# DGCtrl.net
KiCad netlist of a schematic drawn in Altium Designer
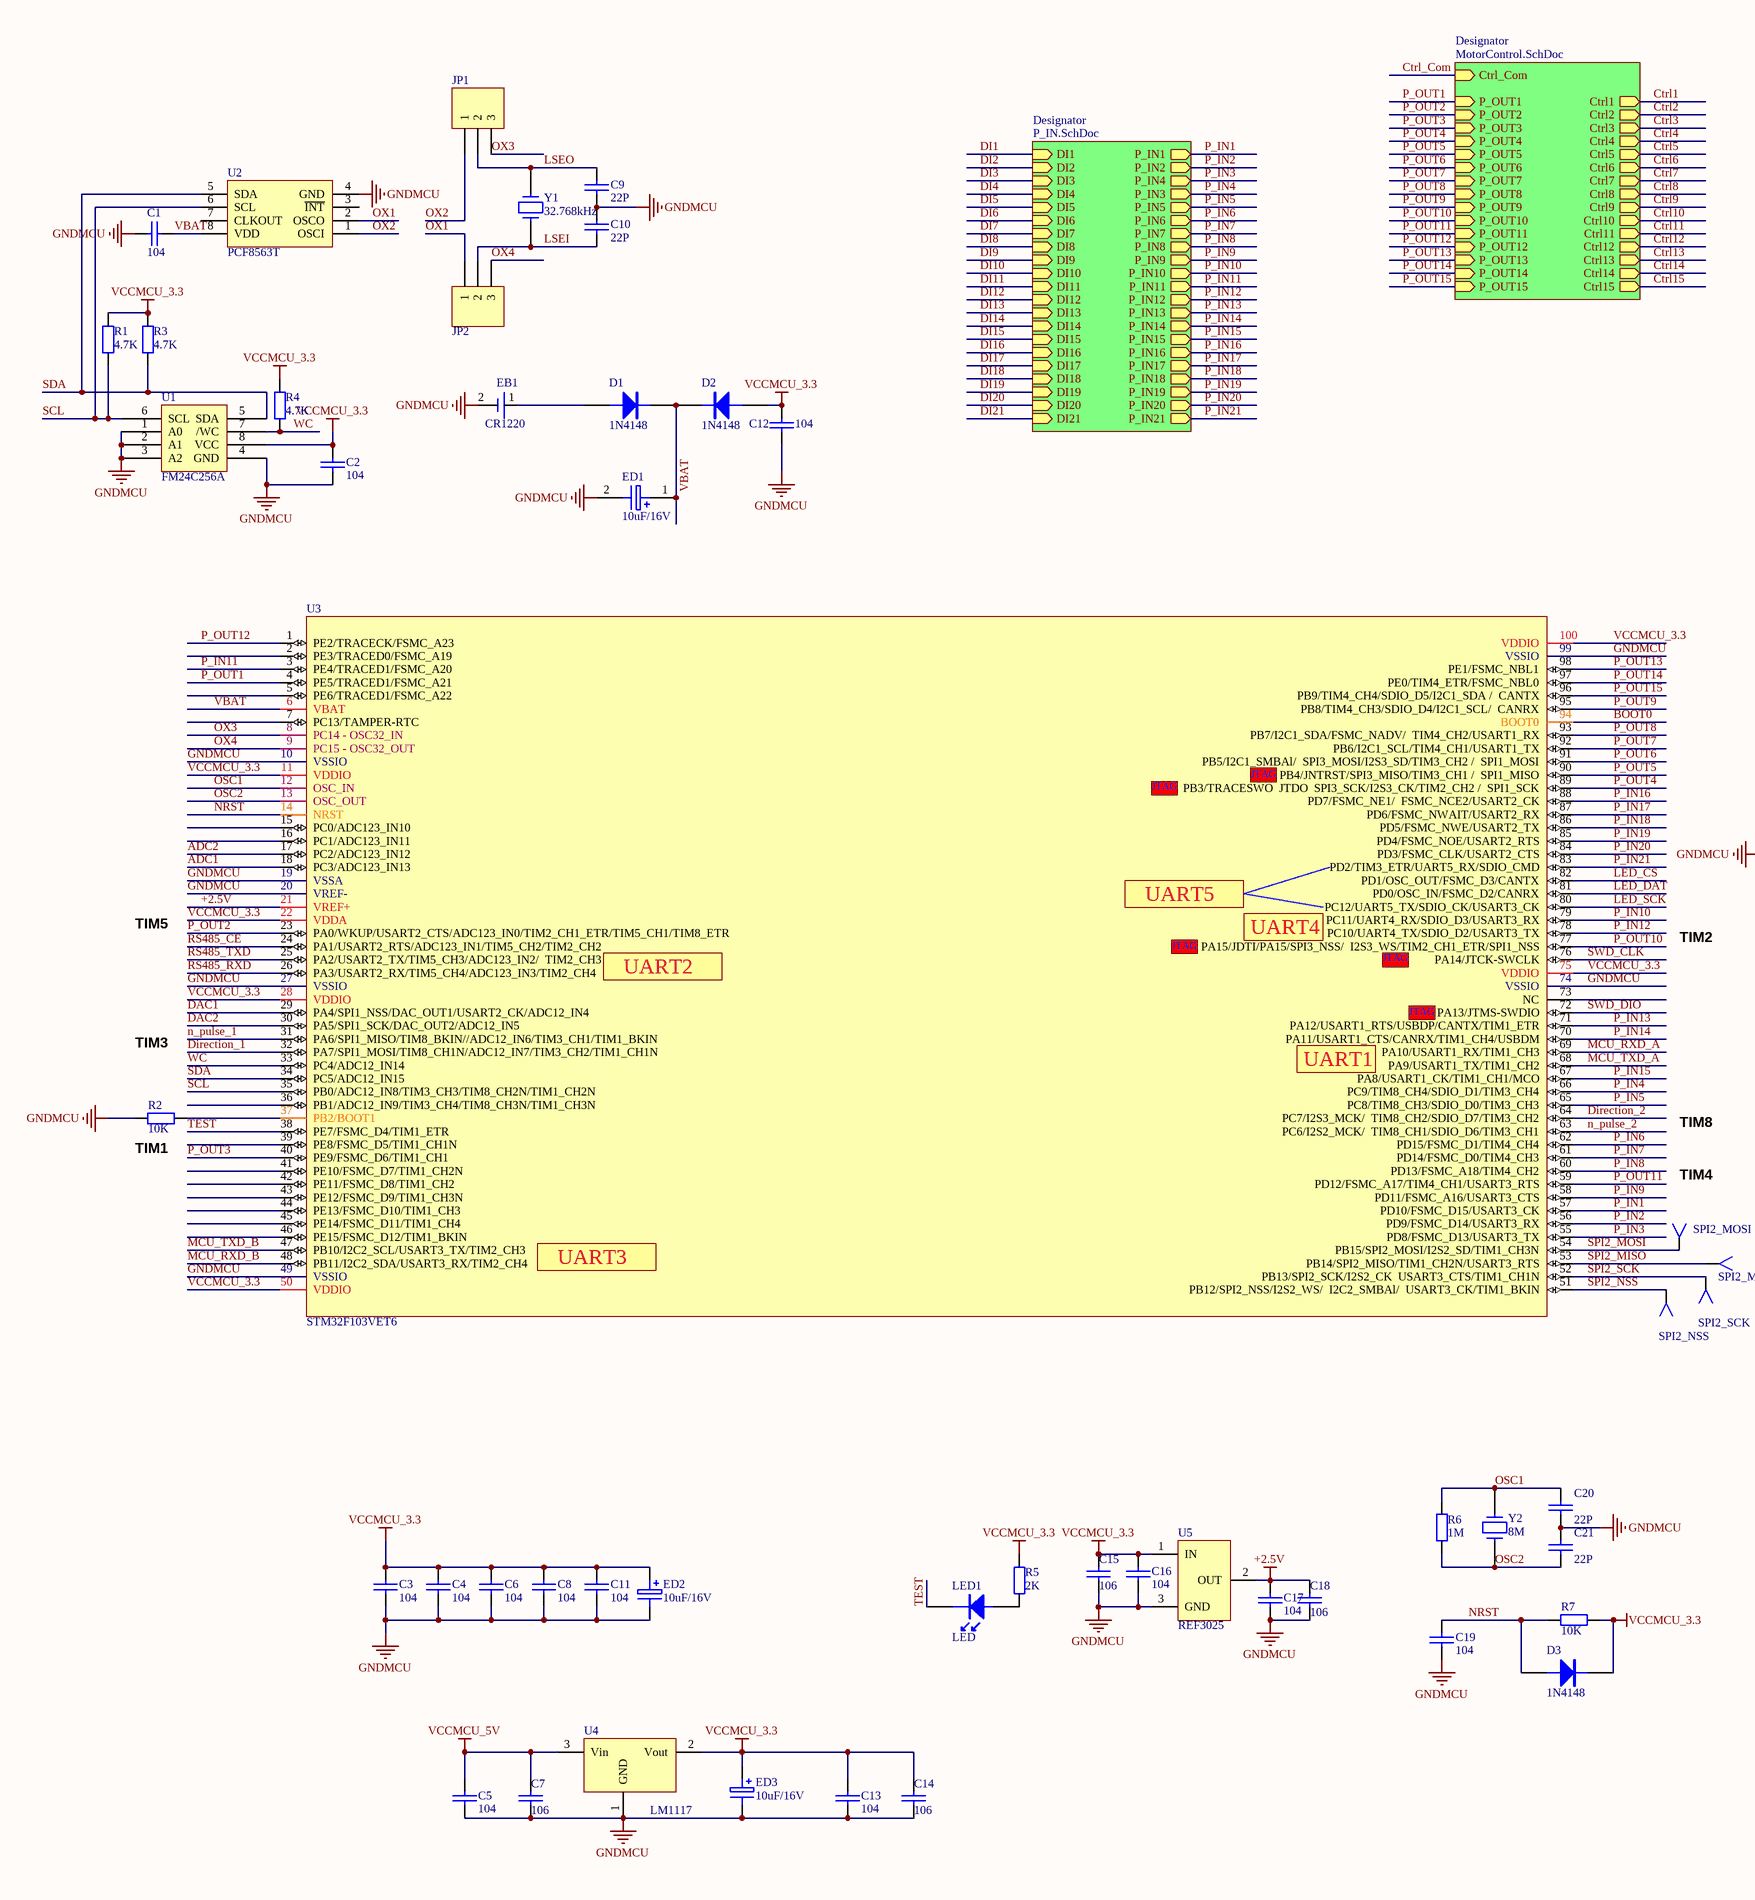
[diagram p0: DGCtrl.SchDoc, left]
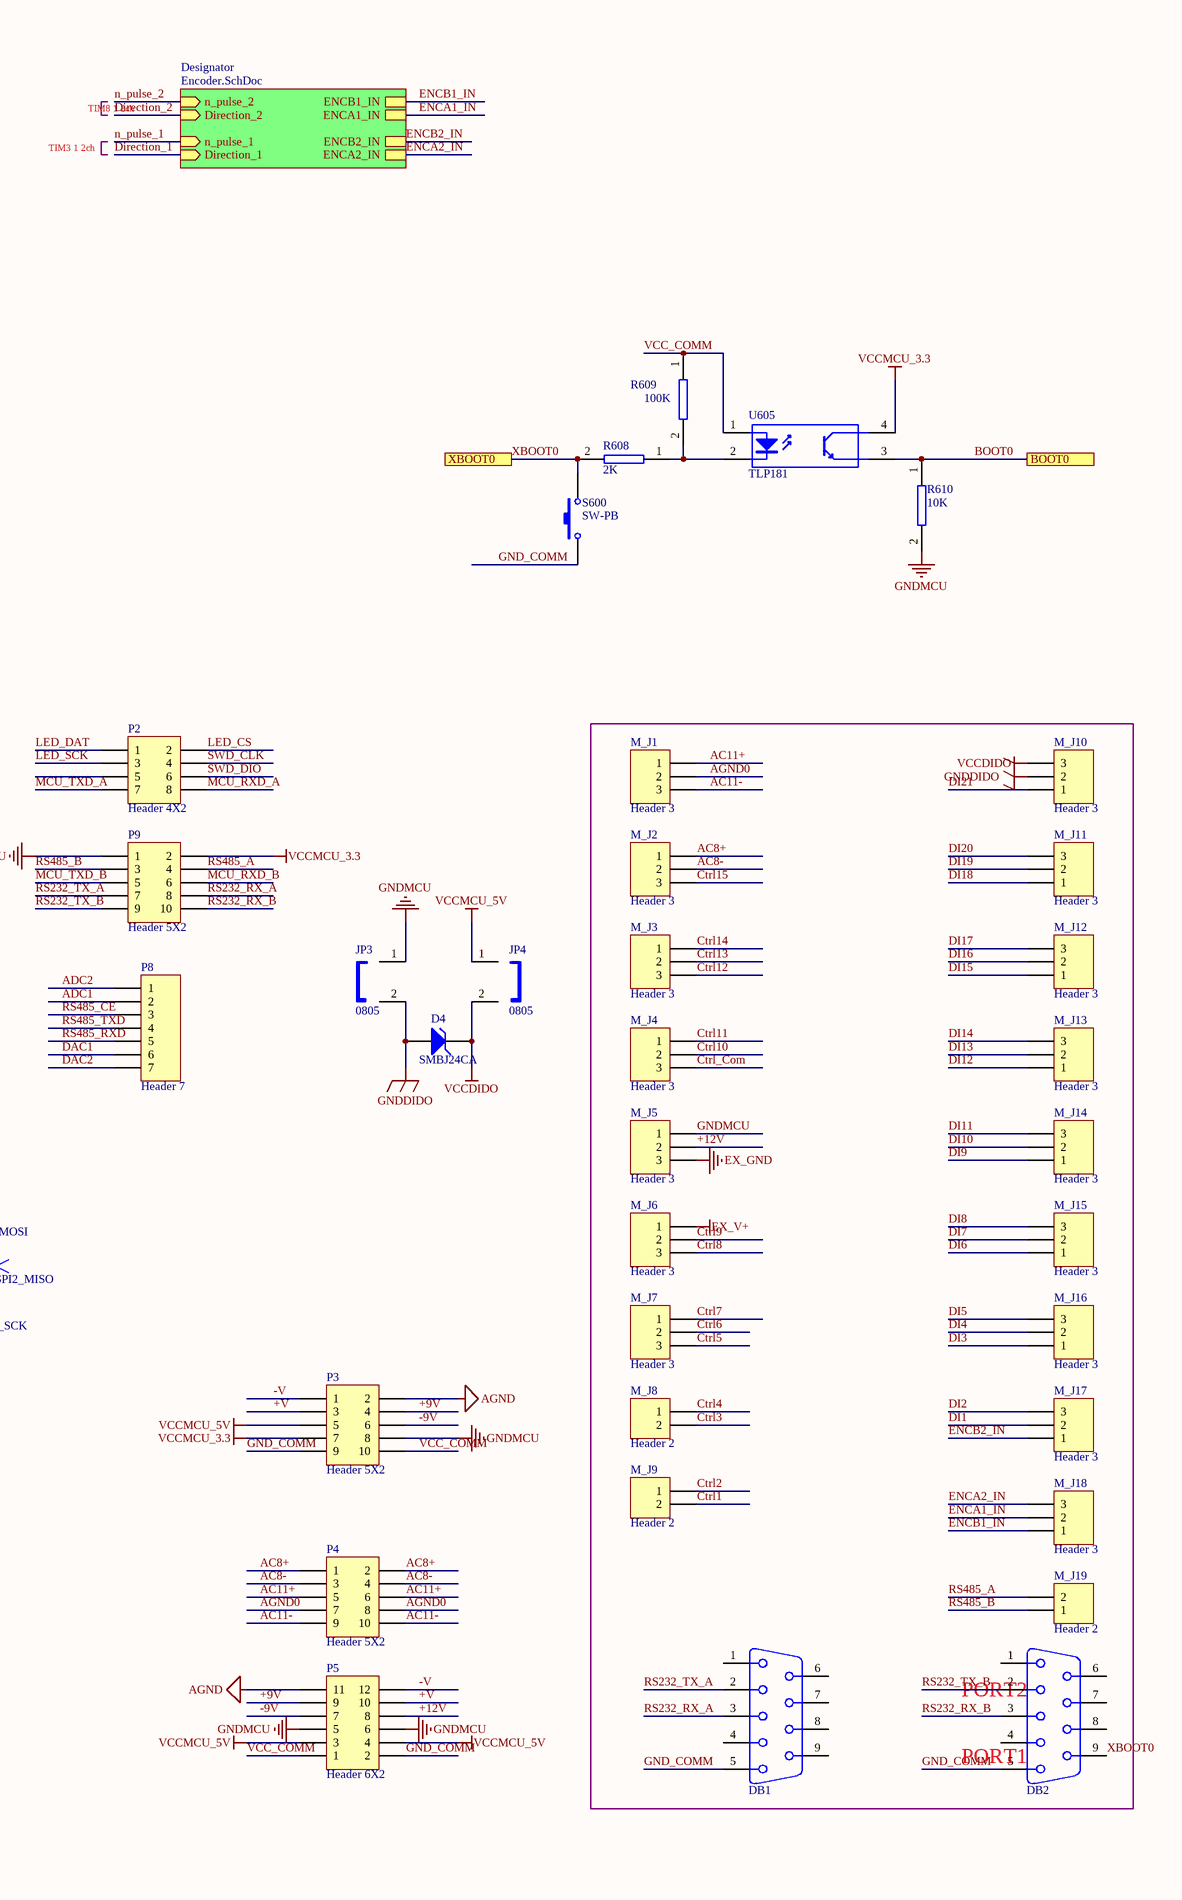
[diagram p1: DGCtrl.SchDoc, right]

(export (version "E")
  (design (tool "Eeschema 10.0.6"))
  (components
    (comp (ref "C1")
      (value "104")
      (footprint "CAPC_E0805_2012X70N")
      (description "Capacitor")
      (libsource (lib "YGInfoSCHLib") (part "CAP"))
    )
    (comp (ref "C2")
      (value "104")
      (footprint "CAPC_E0805_2012X70N")
      (description "Capacitor")
      (libsource (lib "YGInfoSCHLib") (part "CAP"))
    )
    (comp (ref "C3")
      (value "104")
      (footprint "CAPC_E0805_2012X70N")
      (description "Capacitor")
      (libsource (lib "YGInfoSCHLib") (part "CAP"))
    )
    (comp (ref "C4")
      (value "104")
      (footprint "CAPC_E0805_2012X70N")
      (description "Capacitor")
      (libsource (lib "YGInfoSCHLib") (part "CAP"))
    )
    (comp (ref "C5")
      (value "104")
      (footprint "CAPC_E0805_2012X70N")
      (description "Capacitor")
      (libsource (lib "YGInfoSCHLib") (part "CAP"))
    )
    (comp (ref "C6")
      (value "104")
      (footprint "CAPC_E0805_2012X70N")
      (description "Capacitor")
      (libsource (lib "YGInfoSCHLib") (part "CAP"))
    )
    (comp (ref "C7")
      (value "106")
      (footprint "CAPC_E0805_2012X70N")
      (description "Capacitor")
      (libsource (lib "YGInfoSCHLib") (part "CAP"))
    )
    (comp (ref "C8")
      (value "104")
      (footprint "CAPC_E0805_2012X70N")
      (description "Capacitor")
      (libsource (lib "YGInfoSCHLib") (part "CAP"))
    )
    (comp (ref "C9")
      (value "22P")
      (footprint "CAPC_E0805_2012X70N")
      (description "Capacitor")
      (libsource (lib "YGInfoSCHLib") (part "CAP"))
    )
    (comp (ref "C10")
      (value "22P")
      (footprint "CAPC_E0805_2012X70N")
      (description "Capacitor")
      (libsource (lib "YGInfoSCHLib") (part "CAP"))
    )
    (comp (ref "C11")
      (value "104")
      (footprint "CAPC_E0805_2012X70N")
      (description "Capacitor")
      (libsource (lib "YGInfoSCHLib") (part "CAP"))
    )
    (comp (ref "C12")
      (value "104")
      (footprint "CAPC_E0805_2012X70N")
      (description "Capacitor")
      (libsource (lib "YGInfoSCHLib") (part "CAP"))
    )
    (comp (ref "C13")
      (value "104")
      (footprint "CAPC_E0805_2012X70N")
      (description "Capacitor")
      (libsource (lib "YGInfoSCHLib") (part "CAP"))
    )
    (comp (ref "C14")
      (value "106")
      (footprint "CAPC_E0805_2012X70N")
      (description "Capacitor")
      (libsource (lib "YGInfoSCHLib") (part "CAP"))
    )
    (comp (ref "C15")
      (value "106")
      (footprint "CAPC_E0805_2012X70N")
      (description "Capacitor")
      (libsource (lib "YGInfoSCHLib") (part "CAP"))
    )
    (comp (ref "C16")
      (value "104")
      (footprint "CAPC_E0805_2012X70N")
      (description "Capacitor")
      (libsource (lib "YGInfoSCHLib") (part "CAP"))
    )
    (comp (ref "C17")
      (value "104")
      (footprint "CAPC_E0805_2012X70N")
      (description "Capacitor")
      (libsource (lib "YGInfoSCHLib") (part "CAP"))
    )
    (comp (ref "C18")
      (value "106")
      (footprint "CAPC_E0805_2012X70N")
      (description "Capacitor")
      (libsource (lib "YGInfoSCHLib") (part "CAP"))
    )
    (comp (ref "C19")
      (value "104")
      (footprint "CAPC_E0805_2012X70N")
      (description "Capacitor")
      (libsource (lib "YGInfoSCHLib") (part "CAP"))
    )
    (comp (ref "C20")
      (value "22P")
      (footprint "CAPC_E0805_2012X70N")
      (description "Capacitor")
      (libsource (lib "YGInfoSCHLib") (part "CAP"))
    )
    (comp (ref "C21")
      (value "22P")
      (footprint "CAPC_E0805_2012X70N")
      (description "Capacitor")
      (libsource (lib "YGInfoSCHLib") (part "CAP"))
    )
    (comp (ref "D1")
      (value "1N4148")
      (footprint "N4148")
      (description "Diode")
      (libsource (lib "YGInfoSCHLib") (part "DIODE"))
    )
    (comp (ref "D2")
      (value "1N4148")
      (footprint "N4148")
      (description "Diode")
      (libsource (lib "YGInfoSCHLib") (part "DIODE"))
    )
    (comp (ref "D3")
      (value "1N4148")
      (footprint "N4148")
      (description "Diode")
      (libsource (lib "YGInfoSCHLib") (part "DIODE"))
    )
    (comp (ref "D4")
      (value "SMBJ24CA")
      (footprint "SMB")
      (description "Zener Diode")
      (fields (field (name "PUBLISHER") "Altium Limited"))
      (libsource (lib "YGInfoSCHLib") (part "D Zener"))
    )
    (comp (ref "DB1")
      (value "DB9_1")
      (footprint "DB9-DIP")
      (description "Female")
      (libsource (lib "YGInfoSCHLib") (part "DB9_1"))
    )
    (comp (ref "DB2")
      (value "DB9_1")
      (footprint "DB9-DIP")
      (description "Female")
      (libsource (lib "YGInfoSCHLib") (part "DB9_1"))
    )
    (comp (ref "EB1") (value "CR1220") (footprint "CR1220") (libsource (lib "YGInfoSCHLib") (part "E-3.6V")))
    (comp (ref "ED1")
      (value "10uF/16V")
      (footprint "3528")
      (description "Electrolytic Capacitor")
      (libsource (lib "YGInfoSCHLib") (part "ELECTRO1"))
    )
    (comp (ref "ED2") (value "10uF/16V") (footprint "3528") (libsource (lib "") (part "ELECTRO1_1")))
    (comp (ref "ED3") (value "10uF/16V") (footprint "3528") (libsource (lib "") (part "ELECTRO1_1")))
    (comp (ref "JP1")
      (value "Header 3")
      (footprint "JP-3")
      (description "Header, 3-Pin")
      (fields (field (name "PUBLISHER") "Altium Limited"))
      (libsource (lib "YGInfoSCHLib") (part "Header 3"))
    )
    (comp (ref "JP2")
      (value "Header 3")
      (footprint "JP-3")
      (description "Header, 3-Pin")
      (fields (field (name "PUBLISHER") "Altium Limited"))
      (libsource (lib "") (part "Header 3_1"))
    )
    (comp (ref "JP3")
      (value "0805")
      (footprint "RESC_E0805_2012X50N")
      (description "Jumper")
      (libsource (lib "YGInfoSCHLib") (part "JUMPER"))
    )
    (comp (ref "JP4")
      (value "0805")
      (footprint "RESC_E0805_2012X50N")
      (description "Jumper")
      (libsource (lib "YGInfoSCHLib") (part "JUMPER"))
    )
    (comp (ref "LED1") (value "LED") (footprint "LED0805") (libsource (lib "YGInfoSCHLib") (part "LED-PH")))
    (comp (ref "M_J1")
      (value "Header 3")
      (footprint "DG5.08-3")
      (description "Header, 3-Pin")
      (fields (field (name "PUBLISHER") "Altium Limited"))
      (libsource (lib "") (part "Header 3_2"))
    )
    (comp (ref "M_J2")
      (value "Header 3")
      (footprint "DG5.08-3")
      (description "Header, 3-Pin")
      (fields (field (name "PUBLISHER") "Altium Limited"))
      (libsource (lib "") (part "Header 3_2"))
    )
    (comp (ref "M_J3")
      (value "Header 3")
      (footprint "DG5.08-3")
      (description "Header, 3-Pin")
      (fields (field (name "PUBLISHER") "Altium Limited"))
      (libsource (lib "") (part "Header 3_2"))
    )
    (comp (ref "M_J4")
      (value "Header 3")
      (footprint "DG5.08-3")
      (description "Header, 3-Pin")
      (fields (field (name "PUBLISHER") "Altium Limited"))
      (libsource (lib "") (part "Header 3_2"))
    )
    (comp (ref "M_J5")
      (value "Header 3")
      (footprint "DG5.08-3")
      (description "Header, 3-Pin")
      (fields (field (name "PUBLISHER") "Altium Limited"))
      (libsource (lib "") (part "Header 3_2"))
    )
    (comp (ref "M_J6")
      (value "Header 3")
      (footprint "DG5.08-3")
      (description "Header, 3-Pin")
      (fields (field (name "PUBLISHER") "Altium Limited"))
      (libsource (lib "") (part "Header 3_2"))
    )
    (comp (ref "M_J7")
      (value "Header 3")
      (footprint "DG5.08-3")
      (description "Header, 3-Pin")
      (fields (field (name "PUBLISHER") "Altium Limited"))
      (libsource (lib "") (part "Header 3_2"))
    )
    (comp (ref "M_J8")
      (value "Header 2")
      (footprint "DG5.08-2")
      (description "Header, 2-Pin")
      (fields (field (name "PUBLISHER") "Altium Limited"))
      (libsource (lib "YGInfoSCHLib") (part "Header 2"))
    )
    (comp (ref "M_J9")
      (value "Header 2")
      (footprint "DG5.08-2")
      (description "Header, 2-Pin")
      (fields (field (name "PUBLISHER") "Altium Limited"))
      (libsource (lib "YGInfoSCHLib") (part "Header 2"))
    )
    (comp (ref "M_J10")
      (value "Header 3")
      (footprint "DG5.08-3")
      (description "Header, 3-Pin")
      (fields (field (name "PUBLISHER") "Altium Limited"))
      (libsource (lib "YGInfoSCHLib") (part "Header 3"))
    )
    (comp (ref "M_J11")
      (value "Header 3")
      (footprint "DG5.08-3")
      (description "Header, 3-Pin")
      (fields (field (name "PUBLISHER") "Altium Limited"))
      (libsource (lib "YGInfoSCHLib") (part "Header 3"))
    )
    (comp (ref "M_J12")
      (value "Header 3")
      (footprint "DG5.08-3")
      (description "Header, 3-Pin")
      (fields (field (name "PUBLISHER") "Altium Limited"))
      (libsource (lib "YGInfoSCHLib") (part "Header 3"))
    )
    (comp (ref "M_J13")
      (value "Header 3")
      (footprint "DG5.08-3")
      (description "Header, 3-Pin")
      (fields (field (name "PUBLISHER") "Altium Limited"))
      (libsource (lib "YGInfoSCHLib") (part "Header 3"))
    )
    (comp (ref "M_J14")
      (value "Header 3")
      (footprint "DG5.08-3")
      (description "Header, 3-Pin")
      (fields (field (name "PUBLISHER") "Altium Limited"))
      (libsource (lib "YGInfoSCHLib") (part "Header 3"))
    )
    (comp (ref "M_J15")
      (value "Header 3")
      (footprint "DG5.08-3")
      (description "Header, 3-Pin")
      (fields (field (name "PUBLISHER") "Altium Limited"))
      (libsource (lib "YGInfoSCHLib") (part "Header 3"))
    )
    (comp (ref "M_J16")
      (value "Header 3")
      (footprint "DG5.08-3")
      (description "Header, 3-Pin")
      (fields (field (name "PUBLISHER") "Altium Limited"))
      (libsource (lib "YGInfoSCHLib") (part "Header 3"))
    )
    (comp (ref "M_J17")
      (value "Header 3")
      (footprint "DG5.08-3")
      (description "Header, 3-Pin")
      (fields (field (name "PUBLISHER") "Altium Limited"))
      (libsource (lib "YGInfoSCHLib") (part "Header 3"))
    )
    (comp (ref "M_J18")
      (value "Header 3")
      (footprint "DG5.08-3")
      (description "Header, 3-Pin")
      (fields (field (name "PUBLISHER") "Altium Limited"))
      (libsource (lib "YGInfoSCHLib") (part "Header 3"))
    )
    (comp (ref "M_J19")
      (value "Header 2")
      (footprint "DG5.08-2")
      (description "Header, 2-Pin")
      (fields (field (name "PUBLISHER") "Altium Limited"))
      (libsource (lib "") (part "Header 2_1"))
    )
    (comp (ref "P2")
      (value "Header 4X2")
      (footprint "HDR2X4")
      (description "Header, 4-Pin, Dual row")
      (fields (field (name "PUBLISHER") "Altium Limited"))
      (libsource (lib "YGInfoSCHLib") (part "Header 4X2"))
    )
    (comp (ref "P3")
      (value "Header 5X2")
      (footprint "HDR2X5")
      (description "Header, 5-Pin, Dual row")
      (fields (field (name "PUBLISHER") "Altium Limited"))
      (libsource (lib "YGInfoSCHLib") (part "Header 5X2"))
    )
    (comp (ref "P4")
      (value "Header 5X2")
      (footprint "HDR2X5")
      (description "Header, 5-Pin, Dual row")
      (fields (field (name "PUBLISHER") "Altium Limited"))
      (libsource (lib "YGInfoSCHLib") (part "Header 5X2"))
    )
    (comp (ref "P5")
      (value "Header 6X2")
      (footprint "HDR2X6")
      (description "Header, 6-Pin, Dual row")
      (fields (field (name "PUBLISHER") "Altium Limited"))
      (libsource (lib "YGInfoSCHLib") (part "Header 6X2"))
    )
    (comp (ref "P8")
      (value "Header 7")
      (footprint "HDR1X7")
      (description "Header, 7-Pin")
      (fields (field (name "PUBLISHER") "Altium Limited"))
      (libsource (lib "YGInfoSCHLib") (part "Header 7"))
    )
    (comp (ref "P9")
      (value "Header 5X2")
      (footprint "HDR2X5")
      (description "Header, 5-Pin, Dual row")
      (fields (field (name "PUBLISHER") "Altium Limited"))
      (libsource (lib "YGInfoSCHLib") (part "Header 5X2"))
    )
    (comp (ref "R1")
      (value "4.7K")
      (footprint "RESC_E0805_2012X50N")
      (libsource (lib "YGInfoSCHLib") (part "RES1"))
    )
    (comp (ref "R2") (value "10K") (footprint "RESC_E0805_2012X50N") (libsource (lib "") (part "RES1_1")))
    (comp (ref "R3")
      (value "4.7K")
      (footprint "RESC_E0805_2012X50N")
      (libsource (lib "YGInfoSCHLib") (part "RES1"))
    )
    (comp (ref "R4")
      (value "4.7K")
      (footprint "RESC_E0805_2012X50N")
      (libsource (lib "YGInfoSCHLib") (part "RES1"))
    )
    (comp (ref "R5")
      (value "2K")
      (footprint "RESC_E0805_2012X50N")
      (libsource (lib "YGInfoSCHLib") (part "RES1"))
    )
    (comp (ref "R6")
      (value "1M")
      (footprint "RESC_E0805_2012X50N")
      (libsource (lib "YGInfoSCHLib") (part "RES1"))
    )
    (comp (ref "R7") (value "10K") (footprint "RESC_E0805_2012X50N") (libsource (lib "") (part "RES1_1")))
    (comp (ref "R608")
      (value "2K")
      (footprint "RESC_E0805_2012X50N")
      (libsource (lib "YGInfoSCHLib") (part "RES2"))
    )
    (comp (ref "R609")
      (value "100K")
      (footprint "RESC_E0805_2012X50N")
      (libsource (lib "YGInfoSCHLib") (part "RES2"))
    )
    (comp (ref "R610")
      (value "10K")
      (footprint "RESC_E0805_2012X50N")
      (libsource (lib "YGInfoSCHLib") (part "RES2"))
    )
    (comp (ref "S600")
      (value "SW-PB")
      (footprint "my-key2")
      (description "Switch")
      (fields (field (name "PUBLISHER") "Altium Limited"))
      (libsource (lib "YGInfoSCHLib") (part "SW-PB"))
    )
    (comp (ref "SPI2_MISO")
      (value "TestPoint")
      (footprint "Hole")
      (libsource (lib "YGInfoSCHLib") (part "TestPoint"))
    )
    (comp (ref "SPI2_MOSI")
      (value "TestPoint")
      (footprint "Hole")
      (libsource (lib "YGInfoSCHLib") (part "TestPoint"))
    )
    (comp (ref "SPI2_NSS")
      (value "TestPoint")
      (footprint "Hole")
      (libsource (lib "YGInfoSCHLib") (part "TestPoint"))
    )
    (comp (ref "SPI2_SCK")
      (value "TestPoint")
      (footprint "Hole")
      (libsource (lib "YGInfoSCHLib") (part "TestPoint"))
    )
    (comp (ref "U1")
      (value "FM24C256A")
      (footprint "SOP8_208Mil")
      (description "1.7-5.5V宽电压 256K存储")
      (libsource (lib "YGInfoSCHLib") (part "FM24C256A"))
    )
    (comp (ref "U2")
      (value "PCF8563T")
      (footprint "SO-8")
      (description "IIC RTC")
      (libsource (lib "YGInfoSCHLib") (part "PCF8563T"))
    )
    (comp (ref "U3")
      (value "STM32F103VET6")
      (footprint "LQFP-100")
      (description "512K Flash, 64K SRAM,LQFP100")
      (libsource (lib "YGInfoSCHLib") (part "STM32F103VET6"))
    )
    (comp (ref "U4") (value "LM1117") (footprint "SOT-252") (libsource (lib "YGInfoSCHLib") (part "LD1117A")))
    (comp (ref "U5")
      (value "REF3025")
      (footprint "SOT-23")
      (description "2.048V ,HIGH OUTPUT CURRENT: 25mA,HIGH ACCURACY: 0.2%")
      (libsource (lib "YGInfoSCHLib") (part "REF3020"))
    )
    (comp (ref "U605") (value "TLP181") (footprint "TLP181") (libsource (lib "*") (part "N521-1")))
    (comp (ref "Y1")
      (value "32.768kHz")
      (footprint "XTAL2A")
      (description "Crystal")
      (libsource (lib "YGInfoSCHLib") (part "CRYSTAL"))
    )
    (comp (ref "Y2")
      (value "8M")
      (footprint "JZ")
      (description "Crystal")
      (libsource (lib "YGInfoSCHLib") (part "CRYSTAL"))
    )
  )
  (nets
    (net (code "1") (name "+2.5V") (class "Default")
      (node (ref "C17") (pin "1") (pinfunction "1_1") (pintype "passive"))
      (node (ref "C18") (pin "2") (pinfunction "2_2") (pintype "passive"))
      (node (ref "U3") (pin "21") (pinfunction "VREF+_21") (pintype "passive"))
      (node (ref "U5") (pin "2") (pinfunction "OUT_2") (pintype "passive"))
    )
    (net (code "2") (name "/+9V") (class "Default")
      (node (ref "P3") (pin "4") (pinfunction "4_4") (pintype "passive"))
      (node (ref "P5") (pin "9") (pinfunction "9_9") (pintype "passive"))
    )
    (net (code "3") (name "/+12V") (class "Default")
      (node (ref "M_J5") (pin "2") (pinfunction "2_2") (pintype "passive"))
      (node (ref "P5") (pin "8") (pinfunction "8_8") (pintype "passive"))
    )
    (net (code "4") (name "/+V") (class "Default")
      (node (ref "P3") (pin "3") (pinfunction "3_3") (pintype "passive"))
      (node (ref "P5") (pin "10") (pinfunction "10_10") (pintype "passive"))
    )
    (net (code "5") (name "/-9V") (class "Default")
      (node (ref "P3") (pin "6") (pinfunction "6_6") (pintype "passive"))
      (node (ref "P5") (pin "7") (pinfunction "7_7") (pintype "passive"))
    )
    (net (code "6") (name "/-V") (class "Default")
      (node (ref "P3") (pin "1") (pinfunction "1_1") (pintype "passive"))
      (node (ref "P5") (pin "12") (pinfunction "12_12") (pintype "passive"))
    )
    (net (code "7") (name "/AC8+") (class "Default")
      (node (ref "M_J2") (pin "1") (pinfunction "1_1") (pintype "passive"))
      (node (ref "P4") (pin "1") (pinfunction "1_1") (pintype "passive"))
      (node (ref "P4") (pin "2") (pinfunction "2_2") (pintype "passive"))
    )
    (net (code "8") (name "/AC8-") (class "Default")
      (node (ref "M_J2") (pin "2") (pinfunction "2_2") (pintype "passive"))
      (node (ref "P4") (pin "3") (pinfunction "3_3") (pintype "passive"))
      (node (ref "P4") (pin "4") (pinfunction "4_4") (pintype "passive"))
    )
    (net (code "9") (name "/AC11+") (class "Default")
      (node (ref "M_J1") (pin "1") (pinfunction "1_1") (pintype "passive"))
      (node (ref "P4") (pin "5") (pinfunction "5_5") (pintype "passive"))
      (node (ref "P4") (pin "6") (pinfunction "6_6") (pintype "passive"))
    )
    (net (code "10") (name "/AC11-") (class "Default")
      (node (ref "M_J1") (pin "3") (pinfunction "3_3") (pintype "passive"))
      (node (ref "P4") (pin "10") (pinfunction "10_10") (pintype "passive"))
      (node (ref "P4") (pin "9") (pinfunction "9_9") (pintype "passive"))
    )
    (net (code "11") (name "/ADC1") (class "Default")
      (node (ref "P8") (pin "2") (pinfunction "2_2") (pintype "passive"))
      (node (ref "U3") (pin "18") (pinfunction "PC3/ADC123_IN13_18") (pintype "bidirectional"))
    )
    (net (code "12") (name "/ADC2") (class "Default")
      (node (ref "P8") (pin "1") (pinfunction "1_1") (pintype "passive"))
      (node (ref "U3") (pin "17") (pinfunction "PC2/ADC123_IN12_17") (pintype "bidirectional"))
    )
    (net (code "13") (name "/AGND0") (class "Default")
      (node (ref "M_J1") (pin "2") (pinfunction "2_2") (pintype "passive"))
      (node (ref "P4") (pin "7") (pinfunction "7_7") (pintype "passive"))
      (node (ref "P4") (pin "8") (pinfunction "8_8") (pintype "passive"))
    )
    (net (code "14") (name "/BOOT0") (class "Default")
      (node (ref "R610") (pin "1") (pinfunction "1_1") (pintype "passive"))
      (node (ref "U3") (pin "94") (pinfunction "BOOT0_94") (pintype "passive"))
      (node (ref "U605") (pin "3") (pintype "passive"))
    )
    (net (code "15") (name "/Ctrl1") (class "Default")
      (node (ref "M_J9") (pin "2") (pinfunction "2_2") (pintype "passive"))
    )
    (net (code "16") (name "/Ctrl2") (class "Default")
      (node (ref "M_J9") (pin "1") (pinfunction "1_1") (pintype "passive"))
    )
    (net (code "17") (name "/Ctrl3") (class "Default")
      (node (ref "M_J8") (pin "2") (pinfunction "2_2") (pintype "passive"))
    )
    (net (code "18") (name "/Ctrl4") (class "Default")
      (node (ref "M_J8") (pin "1") (pinfunction "1_1") (pintype "passive"))
    )
    (net (code "19") (name "/Ctrl5") (class "Default")
      (node (ref "M_J7") (pin "3") (pinfunction "3_3") (pintype "passive"))
    )
    (net (code "20") (name "/Ctrl6") (class "Default")
      (node (ref "M_J7") (pin "2") (pinfunction "2_2") (pintype "passive"))
    )
    (net (code "21") (name "/Ctrl7") (class "Default")
      (node (ref "M_J7") (pin "1") (pinfunction "1_1") (pintype "passive"))
    )
    (net (code "22") (name "/Ctrl8") (class "Default")
      (node (ref "M_J6") (pin "3") (pinfunction "3_3") (pintype "passive"))
    )
    (net (code "23") (name "/Ctrl9") (class "Default")
      (node (ref "M_J6") (pin "2") (pinfunction "2_2") (pintype "passive"))
    )
    (net (code "24") (name "/Ctrl10") (class "Default")
      (node (ref "M_J4") (pin "2") (pinfunction "2_2") (pintype "passive"))
    )
    (net (code "25") (name "/Ctrl11") (class "Default")
      (node (ref "M_J4") (pin "1") (pinfunction "1_1") (pintype "passive"))
    )
    (net (code "26") (name "/Ctrl12") (class "Default")
      (node (ref "M_J3") (pin "3") (pinfunction "3_3") (pintype "passive"))
    )
    (net (code "27") (name "/Ctrl13") (class "Default")
      (node (ref "M_J3") (pin "2") (pinfunction "2_2") (pintype "passive"))
    )
    (net (code "28") (name "/Ctrl14") (class "Default")
      (node (ref "M_J3") (pin "1") (pinfunction "1_1") (pintype "passive"))
    )
    (net (code "29") (name "/Ctrl15") (class "Default")
      (node (ref "M_J2") (pin "3") (pinfunction "3_3") (pintype "passive"))
    )
    (net (code "30") (name "/Ctrl_Com") (class "Default")
      (node (ref "M_J4") (pin "3") (pinfunction "3_3") (pintype "passive"))
    )
    (net (code "31") (name "/DAC1") (class "Default")
      (node (ref "P8") (pin "6") (pinfunction "6_6") (pintype "passive"))
      (node (ref "U3") (pin "29") (pinfunction "PA4/SPI1_NSS/DAC_OUT1/USART2_CK/ADC12_IN4_29") (pintype "bidirectional"))
    )
    (net (code "32") (name "/DAC2") (class "Default")
      (node (ref "P8") (pin "7") (pinfunction "7_7") (pintype "passive"))
      (node (ref "U3") (pin "30") (pinfunction "PA5/SPI1_SCK/DAC_OUT2/ADC12_IN5_30") (pintype "bidirectional"))
    )
    (net (code "33") (name "/DI1") (class "Default")
      (node (ref "M_J17") (pin "2") (pinfunction "2_2") (pintype "passive"))
    )
    (net (code "34") (name "/DI2") (class "Default")
      (node (ref "M_J17") (pin "3") (pinfunction "3_3") (pintype "passive"))
    )
    (net (code "35") (name "/DI3") (class "Default")
      (node (ref "M_J16") (pin "1") (pinfunction "1_1") (pintype "passive"))
    )
    (net (code "36") (name "/DI4") (class "Default")
      (node (ref "M_J16") (pin "2") (pinfunction "2_2") (pintype "passive"))
    )
    (net (code "37") (name "/DI5") (class "Default")
      (node (ref "M_J16") (pin "3") (pinfunction "3_3") (pintype "passive"))
    )
    (net (code "38") (name "/DI6") (class "Default")
      (node (ref "M_J15") (pin "1") (pinfunction "1_1") (pintype "passive"))
    )
    (net (code "39") (name "/DI7") (class "Default")
      (node (ref "M_J15") (pin "2") (pinfunction "2_2") (pintype "passive"))
    )
    (net (code "40") (name "/DI8") (class "Default")
      (node (ref "M_J15") (pin "3") (pinfunction "3_3") (pintype "passive"))
    )
    (net (code "41") (name "/DI9") (class "Default")
      (node (ref "M_J14") (pin "1") (pinfunction "1_1") (pintype "passive"))
    )
    (net (code "42") (name "/DI10") (class "Default")
      (node (ref "M_J14") (pin "2") (pinfunction "2_2") (pintype "passive"))
    )
    (net (code "43") (name "/DI11") (class "Default")
      (node (ref "M_J14") (pin "3") (pinfunction "3_3") (pintype "passive"))
    )
    (net (code "44") (name "/DI12") (class "Default")
      (node (ref "M_J13") (pin "1") (pinfunction "1_1") (pintype "passive"))
    )
    (net (code "45") (name "/DI13") (class "Default")
      (node (ref "M_J13") (pin "2") (pinfunction "2_2") (pintype "passive"))
    )
    (net (code "46") (name "/DI14") (class "Default")
      (node (ref "M_J13") (pin "3") (pinfunction "3_3") (pintype "passive"))
    )
    (net (code "47") (name "/DI15") (class "Default")
      (node (ref "M_J12") (pin "1") (pinfunction "1_1") (pintype "passive"))
    )
    (net (code "48") (name "/DI16") (class "Default")
      (node (ref "M_J12") (pin "2") (pinfunction "2_2") (pintype "passive"))
    )
    (net (code "49") (name "/DI17") (class "Default")
      (node (ref "M_J12") (pin "3") (pinfunction "3_3") (pintype "passive"))
    )
    (net (code "50") (name "/DI18") (class "Default")
      (node (ref "M_J11") (pin "1") (pinfunction "1_1") (pintype "passive"))
    )
    (net (code "51") (name "/DI19") (class "Default")
      (node (ref "M_J11") (pin "2") (pinfunction "2_2") (pintype "passive"))
    )
    (net (code "52") (name "/DI20") (class "Default")
      (node (ref "M_J11") (pin "3") (pinfunction "3_3") (pintype "passive"))
    )
    (net (code "53") (name "/DI21") (class "Default")
      (node (ref "M_J10") (pin "1") (pinfunction "1_1") (pintype "passive"))
    )
    (net (code "54") (name "/Direction_1") (class "Default")
      (node (ref "U3") (pin "32") (pinfunction "PA7/SPI1_MOSI/TIM8_CH1N/ADC12_IN7/TIM3_CH2/TIM1_CH1N_32") (pintype "bidirectional"))
    )
    (net (code "55") (name "/Direction_2") (class "Default")
      (node (ref "U3") (pin "64") (pinfunction "PC7/I2S3_MCK/__TIM8_CH2/SDIO_D7/TIM3_CH2_64") (pintype "bidirectional"))
    )
    (net (code "56") (name "/ENCA1_IN") (class "Default")
      (node (ref "M_J18") (pin "2") (pinfunction "2_2") (pintype "passive"))
    )
    (net (code "57") (name "/ENCA2_IN") (class "Default")
      (node (ref "M_J18") (pin "3") (pinfunction "3_3") (pintype "passive"))
    )
    (net (code "58") (name "/ENCB1_IN") (class "Default")
      (node (ref "M_J18") (pin "1") (pinfunction "1_1") (pintype "passive"))
    )
    (net (code "59") (name "/ENCB2_IN") (class "Default")
      (node (ref "M_J17") (pin "1") (pinfunction "1_1") (pintype "passive"))
    )
    (net (code "60") (name "/GND_COMM") (class "Default")
      (node (ref "DB1") (pin "5") (pinfunction "GND_5") (pintype "passive"))
      (node (ref "DB2") (pin "5") (pinfunction "GND_5") (pintype "passive"))
      (node (ref "P3") (pin "9") (pinfunction "9_9") (pintype "passive"))
      (node (ref "P5") (pin "2") (pinfunction "2_2") (pintype "passive"))
      (node (ref "S600") (pin "1") (pinfunction "1_1") (pintype "passive"))
    )
    (net (code "61") (name "/LED_CS") (class "Default")
      (node (ref "P2") (pin "2") (pinfunction "2_2") (pintype "passive"))
      (node (ref "U3") (pin "82") (pinfunction "PD1/OSC_OUT/FSMC_D3/CANTX_82") (pintype "bidirectional"))
    )
    (net (code "62") (name "/LED_DAT") (class "Default")
      (node (ref "P2") (pin "1") (pinfunction "1_1") (pintype "passive"))
      (node (ref "U3") (pin "81") (pinfunction "PD0/OSC_IN/FSMC_D2/CANRX_81") (pintype "bidirectional"))
    )
    (net (code "63") (name "/LED_SCK") (class "Default")
      (node (ref "P2") (pin "3") (pinfunction "3_3") (pintype "passive"))
      (node (ref "U3") (pin "80") (pinfunction "PC12/UART5_TX/SDIO_CK/USART3_CK_80") (pintype "bidirectional"))
    )
    (net (code "64") (name "/LSEI") (class "Default")
      (node (ref "C10") (pin "2") (pinfunction "2_2") (pintype "passive"))
      (node (ref "JP2") (pin "2") (pinfunction "2_2") (pintype "passive"))
      (node (ref "Y1") (pin "2") (pinfunction "2_2") (pintype "passive"))
    )
    (net (code "65") (name "/LSEO") (class "Default")
      (node (ref "C9") (pin "1") (pinfunction "1_1") (pintype "passive"))
      (node (ref "JP1") (pin "2") (pinfunction "2_2") (pintype "passive"))
      (node (ref "Y1") (pin "1") (pinfunction "1_1") (pintype "passive"))
    )
    (net (code "66") (name "/MCU_RXD_A") (class "Default")
      (node (ref "P2") (pin "8") (pinfunction "8_8") (pintype "passive"))
      (node (ref "U3") (pin "69") (pinfunction "PA10/USART1_RX/TIM1_CH3_69") (pintype "bidirectional"))
    )
    (net (code "67") (name "/MCU_RXD_B") (class "Default")
      (node (ref "P9") (pin "6") (pinfunction "6_6") (pintype "passive"))
      (node (ref "U3") (pin "48") (pinfunction "PB11/I2C2_SDA/USART3_RX/TIM2_CH4_48") (pintype "bidirectional"))
    )
    (net (code "68") (name "/MCU_TXD_A") (class "Default")
      (node (ref "P2") (pin "7") (pinfunction "7_7") (pintype "passive"))
      (node (ref "U3") (pin "68") (pinfunction "PA9/USART1_TX/TIM1_CH2_68") (pintype "bidirectional"))
    )
    (net (code "69") (name "/MCU_TXD_B") (class "Default")
      (node (ref "P9") (pin "5") (pinfunction "5_5") (pintype "passive"))
      (node (ref "U3") (pin "47") (pinfunction "PB10/I2C2_SCL/USART3_TX/TIM2_CH3_47") (pintype "bidirectional"))
    )
    (net (code "70") (name "/NRST") (class "Default")
      (node (ref "C19") (pin "1") (pinfunction "1_1") (pintype "passive"))
      (node (ref "D3") (pin "1") (pinfunction "A_1") (pintype "passive"))
      (node (ref "R7") (pin "1") (pinfunction "1_1") (pintype "passive"))
      (node (ref "U3") (pin "14") (pinfunction "NRST_14") (pintype "passive"))
    )
    (net (code "71") (name "/OSC1") (class "Default")
      (node (ref "C20") (pin "2") (pinfunction "2_2") (pintype "passive"))
      (node (ref "R6") (pin "2") (pinfunction "2_2") (pintype "passive"))
      (node (ref "U3") (pin "12") (pinfunction "OSC_IN_12") (pintype "passive"))
      (node (ref "Y2") (pin "2") (pinfunction "2_2") (pintype "passive"))
    )
    (net (code "72") (name "/OSC2") (class "Default")
      (node (ref "C21") (pin "1") (pinfunction "1_1") (pintype "passive"))
      (node (ref "R6") (pin "1") (pinfunction "1_1") (pintype "passive"))
      (node (ref "U3") (pin "13") (pinfunction "OSC_OUT_13") (pintype "passive"))
      (node (ref "Y2") (pin "1") (pinfunction "1_1") (pintype "passive"))
    )
    (net (code "73") (name "/OX1") (class "Default")
      (node (ref "JP2") (pin "1") (pinfunction "1_1") (pintype "passive"))
      (node (ref "U2") (pin "2") (pinfunction "OSCO_2") (pintype "passive"))
    )
    (net (code "74") (name "/OX2") (class "Default")
      (node (ref "JP1") (pin "1") (pinfunction "1_1") (pintype "passive"))
      (node (ref "U2") (pin "1") (pinfunction "OSCI_1") (pintype "passive"))
    )
    (net (code "75") (name "/OX3") (class "Default")
      (node (ref "JP1") (pin "3") (pinfunction "3_3") (pintype "passive"))
      (node (ref "U3") (pin "8") (pinfunction "PC14_-_OSC32_IN_8") (pintype "passive"))
    )
    (net (code "76") (name "/OX4") (class "Default")
      (node (ref "JP2") (pin "3") (pinfunction "3_3") (pintype "passive"))
      (node (ref "U3") (pin "9") (pinfunction "PC15_-_OSC32_OUT_9") (pintype "passive"))
    )
    (net (code "77") (name "/P_IN1") (class "Default")
      (node (ref "U3") (pin "57") (pinfunction "PD10/FSMC_D15/USART3_CK_57") (pintype "bidirectional"))
    )
    (net (code "78") (name "/P_IN2") (class "Default")
      (node (ref "U3") (pin "56") (pinfunction "PD9/FSMC_D14/USART3_RX_56") (pintype "bidirectional"))
    )
    (net (code "79") (name "/P_IN3") (class "Default")
      (node (ref "U3") (pin "55") (pinfunction "PD8/FSMC_D13/USART3_TX_55") (pintype "bidirectional"))
    )
    (net (code "80") (name "/P_IN4") (class "Default")
      (node (ref "U3") (pin "66") (pinfunction "PC9/TIM8_CH4/SDIO_D1/TIM3_CH4_66") (pintype "bidirectional"))
    )
    (net (code "81") (name "/P_IN5") (class "Default")
      (node (ref "U3") (pin "65") (pinfunction "PC8/TIM8_CH3/SDIO_D0/TIM3_CH3_65") (pintype "bidirectional"))
    )
    (net (code "82") (name "/P_IN6") (class "Default")
      (node (ref "U3") (pin "62") (pinfunction "PD15/FSMC_D1/TIM4_CH4_62") (pintype "bidirectional"))
    )
    (net (code "83") (name "/P_IN7") (class "Default")
      (node (ref "U3") (pin "61") (pinfunction "PD14/FSMC_D0/TIM4_CH3_61") (pintype "bidirectional"))
    )
    (net (code "84") (name "/P_IN8") (class "Default")
      (node (ref "U3") (pin "60") (pinfunction "PD13/FSMC_A18/TIM4_CH2_60") (pintype "bidirectional"))
    )
    (net (code "85") (name "/P_IN9") (class "Default")
      (node (ref "U3") (pin "58") (pinfunction "PD11/FSMC_A16/USART3_CTS_58") (pintype "bidirectional"))
    )
    (net (code "86") (name "/P_IN10") (class "Default")
      (node (ref "U3") (pin "79") (pinfunction "PC11/UART4_RX/SDIO_D3/USART3_RX_79") (pintype "bidirectional"))
    )
    (net (code "87") (name "/P_IN11") (class "Default")
      (node (ref "U3") (pin "3") (pinfunction "PE4/TRACED1/FSMC_A20_3") (pintype "bidirectional"))
    )
    (net (code "88") (name "/P_IN12") (class "Default")
      (node (ref "U3") (pin "78") (pinfunction "PC10/UART4_TX/SDIO_D2/USART3_TX_78") (pintype "bidirectional"))
    )
    (net (code "89") (name "/P_IN13") (class "Default")
      (node (ref "U3") (pin "71") (pinfunction "PA12/USART1_RTS/USBDP/CANTX/TIM1_ETR_71") (pintype "bidirectional"))
    )
    (net (code "90") (name "/P_IN14") (class "Default")
      (node (ref "U3") (pin "70") (pinfunction "PA11/USART1_CTS/CANRX/TIM1_CH4/USBDM_70") (pintype "bidirectional"))
    )
    (net (code "91") (name "/P_IN15") (class "Default")
      (node (ref "U3") (pin "67") (pinfunction "PA8/USART1_CK/TIM1_CH1/MCO_67") (pintype "bidirectional"))
    )
    (net (code "92") (name "/P_IN16") (class "Default")
      (node (ref "U3") (pin "88") (pinfunction "PD7/FSMC_NE1/__FSMC_NCE2/USART2_CK_88") (pintype "bidirectional"))
    )
    (net (code "93") (name "/P_IN17") (class "Default")
      (node (ref "U3") (pin "87") (pinfunction "PD6/FSMC_NWAIT/USART2_RX_87") (pintype "bidirectional"))
    )
    (net (code "94") (name "/P_IN18") (class "Default")
      (node (ref "U3") (pin "86") (pinfunction "PD5/FSMC_NWE/USART2_TX_86") (pintype "bidirectional"))
    )
    (net (code "95") (name "/P_IN19") (class "Default")
      (node (ref "U3") (pin "85") (pinfunction "PD4/FSMC_NOE/USART2_RTS_85") (pintype "bidirectional"))
    )
    (net (code "96") (name "/P_IN20") (class "Default")
      (node (ref "U3") (pin "84") (pinfunction "PD3/FSMC_CLK/USART2_CTS_84") (pintype "bidirectional"))
    )
    (net (code "97") (name "/P_IN21") (class "Default")
      (node (ref "U3") (pin "83") (pinfunction "PD2/TIM3_ETR/UART5_RX/SDIO_CMD_83") (pintype "bidirectional"))
    )
    (net (code "98") (name "/P_OUT1") (class "Default")
      (node (ref "U3") (pin "4") (pinfunction "PE5/TRACED1/FSMC_A21_4") (pintype "bidirectional"))
    )
    (net (code "99") (name "/P_OUT2") (class "Default")
      (node (ref "U3") (pin "23") (pinfunction "PA0/WKUP/USART2_CTS/ADC123_IN0/TIM2_CH1_ETR/TIM5_CH1/TIM8_ETR_23") (pintype "bidirectional"))
    )
    (net (code "100") (name "/P_OUT3") (class "Default")
      (node (ref "U3") (pin "40") (pinfunction "PE9/FSMC_D6/TIM1_CH1_40") (pintype "bidirectional"))
    )
    (net (code "101") (name "/P_OUT4") (class "Default")
      (node (ref "U3") (pin "89") (pinfunction "PB3/TRACESWO__JTDO__SPI3_SCK/I2S3_CK/TIM2_CH2_/__SPI1_SCK_89") (pintype "bidirectional"))
    )
    (net (code "102") (name "/P_OUT5") (class "Default")
      (node (ref "U3") (pin "90") (pinfunction "PB4/JNTRST/SPI3_MISO/TIM3_CH1_/__SPI1_MISO_90") (pintype "bidirectional"))
    )
    (net (code "103") (name "/P_OUT6") (class "Default")
      (node (ref "U3") (pin "91") (pinfunction "PB5/I2C1_SMBAl/__SPI3_MOSI/I2S3_SD/TIM3_CH2_/__SPI1_MOSI_91") (pintype "bidirectional"))
    )
    (net (code "104") (name "/P_OUT7") (class "Default")
      (node (ref "U3") (pin "92") (pinfunction "PB6/I2C1_SCL/TIM4_CH1/USART1_TX_92") (pintype "bidirectional"))
    )
    (net (code "105") (name "/P_OUT8") (class "Default")
      (node (ref "U3") (pin "93") (pinfunction "PB7/I2C1_SDA/FSMC_NADV/__TIM4_CH2/USART1_RX_93") (pintype "bidirectional"))
    )
    (net (code "106") (name "/P_OUT9") (class "Default")
      (node (ref "U3") (pin "95") (pinfunction "PB8/TIM4_CH3/SDIO_D4/I2C1_SCL/__CANRX_95") (pintype "bidirectional"))
    )
    (net (code "107") (name "/P_OUT10") (class "Default")
      (node (ref "U3") (pin "77") (pinfunction "PA15/JDTI/PA15/SPI3_NSS/__I2S3_WS/TIM2_CH1_ETR/SPI1_NSS_77") (pintype "bidirectional"))
    )
    (net (code "108") (name "/P_OUT11") (class "Default")
      (node (ref "U3") (pin "59") (pinfunction "PD12/FSMC_A17/TIM4_CH1/USART3_RTS_59") (pintype "bidirectional"))
    )
    (net (code "109") (name "/P_OUT12") (class "Default")
      (node (ref "U3") (pin "1") (pinfunction "PE2/TRACECK/FSMC_A23_1") (pintype "bidirectional"))
    )
    (net (code "110") (name "/P_OUT13") (class "Default")
      (node (ref "U3") (pin "98") (pinfunction "PE1/FSMC_NBL1_98") (pintype "bidirectional"))
    )
    (net (code "111") (name "/P_OUT14") (class "Default")
      (node (ref "U3") (pin "97") (pinfunction "PE0/TIM4_ETR/FSMC_NBL0_97") (pintype "bidirectional"))
    )
    (net (code "112") (name "/P_OUT15") (class "Default")
      (node (ref "U3") (pin "96") (pinfunction "PB9/TIM4_CH4/SDIO_D5/I2C1_SDA_/__CANTX_96") (pintype "bidirectional"))
    )
    (net (code "113") (name "/RS232_RX_A") (class "Default")
      (node (ref "DB1") (pin "3") (pinfunction "TXD_3") (pintype "passive"))
      (node (ref "P9") (pin "8") (pinfunction "8_8") (pintype "passive"))
    )
    (net (code "114") (name "/RS232_RX_B") (class "Default")
      (node (ref "DB2") (pin "3") (pinfunction "TXD_3") (pintype "passive"))
      (node (ref "P9") (pin "10") (pinfunction "10_10") (pintype "passive"))
    )
    (net (code "115") (name "/RS232_TX_A") (class "Default")
      (node (ref "DB1") (pin "2") (pinfunction "RXD_2") (pintype "passive"))
      (node (ref "P9") (pin "7") (pinfunction "7_7") (pintype "passive"))
    )
    (net (code "116") (name "/RS232_TX_B") (class "Default")
      (node (ref "DB2") (pin "2") (pinfunction "RXD_2") (pintype "passive"))
      (node (ref "P9") (pin "9") (pinfunction "9_9") (pintype "passive"))
    )
    (net (code "117") (name "/RS485_A") (class "Default")
      (node (ref "M_J19") (pin "2") (pinfunction "2_2") (pintype "passive"))
      (node (ref "P9") (pin "4") (pinfunction "4_4") (pintype "passive"))
    )
    (net (code "118") (name "/RS485_B") (class "Default")
      (node (ref "M_J19") (pin "1") (pinfunction "1_1") (pintype "passive"))
      (node (ref "P9") (pin "3") (pinfunction "3_3") (pintype "passive"))
    )
    (net (code "119") (name "/RS485_CE") (class "Default")
      (node (ref "P8") (pin "3") (pinfunction "3_3") (pintype "passive"))
      (node (ref "U3") (pin "24") (pinfunction "PA1/USART2_RTS/ADC123_IN1/TIM5_CH2/TIM2_CH2_24") (pintype "bidirectional"))
    )
    (net (code "120") (name "/RS485_RXD") (class "Default")
      (node (ref "P8") (pin "5") (pinfunction "5_5") (pintype "passive"))
      (node (ref "U3") (pin "26") (pinfunction "PA3/USART2_RX/TIM5_CH4/ADC123_IN3/TIM2_CH4_26") (pintype "bidirectional"))
    )
    (net (code "121") (name "/RS485_TXD") (class "Default")
      (node (ref "P8") (pin "4") (pinfunction "4_4") (pintype "passive"))
      (node (ref "U3") (pin "25") (pinfunction "PA2/USART2_TX/TIM5_CH3/ADC123_IN2/__TIM2_CH3_25") (pintype "bidirectional"))
    )
    (net (code "122") (name "/SCL") (class "Default")
      (node (ref "R1") (pin "1") (pinfunction "1_1") (pintype "passive"))
      (node (ref "U1") (pin "6") (pinfunction "SCL_6") (pintype "passive"))
      (node (ref "U2") (pin "6") (pinfunction "SCL_6") (pintype "passive"))
      (node (ref "U3") (pin "35") (pinfunction "PB0/ADC12_IN8/TIM3_CH3/TIM8_CH2N/TIM1_CH2N_35") (pintype "bidirectional"))
    )
    (net (code "123") (name "/SDA") (class "Default")
      (node (ref "R3") (pin "1") (pinfunction "1_1") (pintype "passive"))
      (node (ref "U1") (pin "5") (pinfunction "SDA_5") (pintype "passive"))
      (node (ref "U2") (pin "5") (pinfunction "SDA_5") (pintype "passive"))
      (node (ref "U3") (pin "34") (pinfunction "PC5/ADC12_IN15_34") (pintype "bidirectional"))
    )
    (net (code "124") (name "/SPI2_MISO") (class "Default")
      (node (ref "SPI2_MISO") (pin "1") (pinfunction "1_1") (pintype "power_in"))
      (node (ref "U3") (pin "53") (pinfunction "PB14/SPI2_MISO/TIM1_CH2N/USART3_RTS_53") (pintype "bidirectional"))
    )
    (net (code "125") (name "/SPI2_MOSI") (class "Default")
      (node (ref "SPI2_MOSI") (pin "1") (pinfunction "1_1") (pintype "power_in"))
      (node (ref "U3") (pin "54") (pinfunction "PB15/SPI2_MOSI/I2S2_SD/TIM1_CH3N_54") (pintype "bidirectional"))
    )
    (net (code "126") (name "/SPI2_NSS") (class "Default")
      (node (ref "SPI2_NSS") (pin "1") (pinfunction "1_1") (pintype "power_in"))
      (node (ref "U3") (pin "51") (pinfunction "PB12/SPI2_NSS/I2S2_WS/__I2C2_SMBAl/__USART3_CK/TIM1_BKIN_51") (pintype "bidirectional"))
    )
    (net (code "127") (name "/SPI2_SCK") (class "Default")
      (node (ref "SPI2_SCK") (pin "1") (pinfunction "1_1") (pintype "power_in"))
      (node (ref "U3") (pin "52") (pinfunction "PB13/SPI2_SCK/I2S2_CK__USART3_CTS/TIM1_CH1N_52") (pintype "bidirectional"))
    )
    (net (code "128") (name "/SWD_CLK") (class "Default")
      (node (ref "P2") (pin "4") (pinfunction "4_4") (pintype "passive"))
      (node (ref "U3") (pin "76") (pinfunction "PA14/JTCK-SWCLK_76") (pintype "bidirectional"))
    )
    (net (code "129") (name "/SWD_DIO") (class "Default")
      (node (ref "P2") (pin "6") (pinfunction "6_6") (pintype "passive"))
      (node (ref "U3") (pin "72") (pinfunction "PA13/JTMS-SWDIO_72") (pintype "bidirectional"))
    )
    (net (code "130") (name "/TEST") (class "Default")
      (node (ref "LED1") (pin "2") (pinfunction "2_2") (pintype "passive"))
      (node (ref "U3") (pin "38") (pinfunction "PE7/FSMC_D4/TIM1_ETR_38") (pintype "bidirectional"))
    )
    (net (code "131") (name "/VBAT") (class "Default")
      (node (ref "C1") (pin "1") (pinfunction "1_1") (pintype "passive"))
      (node (ref "D1") (pin "2") (pinfunction "K_2") (pintype "passive"))
      (node (ref "D2") (pin "2") (pinfunction "K_2") (pintype "passive"))
      (node (ref "ED1") (pin "1") (pinfunction "1_1") (pintype "passive"))
      (node (ref "U2") (pin "8") (pinfunction "VDD_8") (pintype "passive"))
      (node (ref "U3") (pin "6") (pinfunction "VBAT_6") (pintype "passive"))
    )
    (net (code "132") (name "/VCC_COMM") (class "Default")
      (node (ref "P3") (pin "10") (pinfunction "10_10") (pintype "passive"))
      (node (ref "P5") (pin "1") (pinfunction "1_1") (pintype "passive"))
      (node (ref "R609") (pin "1") (pinfunction "1_1") (pintype "passive"))
      (node (ref "U605") (pin "1") (pintype "passive"))
    )
    (net (code "133") (name "/WC") (class "Default")
      (node (ref "R4") (pin "1") (pinfunction "1_1") (pintype "passive"))
      (node (ref "U1") (pin "7") (pinfunction "/WC_7") (pintype "passive"))
      (node (ref "U3") (pin "33") (pinfunction "PC4/ADC12_IN14_33") (pintype "bidirectional"))
    )
    (net (code "134") (name "/XBOOT0") (class "Default")
      (node (ref "DB2") (pin "9") (pinfunction "DELL_9") (pintype "passive"))
      (node (ref "R608") (pin "2") (pinfunction "2_2") (pintype "passive"))
      (node (ref "S600") (pin "2") (pinfunction "2_2") (pintype "passive"))
    )
    (net (code "135") (name "/n_pulse_1") (class "Default")
      (node (ref "U3") (pin "31") (pinfunction "PA6/SPI1_MISO/TIM8_BKIN//ADC12_IN6/TIM3_CH1/TIM1_BKIN_31") (pintype "bidirectional"))
    )
    (net (code "136") (name "/n_pulse_2") (class "Default")
      (node (ref "U3") (pin "63") (pinfunction "PC6/I2S2_MCK/__TIM8_CH1/SDIO_D6/TIM3_CH1_63") (pintype "bidirectional"))
    )
    (net (code "137") (name "AGND") (class "Default")
      (node (ref "P3") (pin "2") (pinfunction "2_2") (pintype "passive"))
      (node (ref "P5") (pin "11") (pinfunction "11_11") (pintype "passive"))
    )
    (net (code "138") (name "EX_GND") (class "Default")
      (node (ref "M_J5") (pin "3") (pinfunction "3_3") (pintype "passive"))
    )
    (net (code "139") (name "EX_V+") (class "Default")
      (node (ref "M_J6") (pin "1") (pinfunction "1_1") (pintype "passive"))
    )
    (net (code "140") (name "GNDDIDO") (class "Default")
      (node (ref "D4") (pin "1") (pinfunction "A_1") (pintype "passive"))
      (node (ref "JP3") (pin "2") (pinfunction "2_2") (pintype "passive"))
      (node (ref "M_J10") (pin "2") (pinfunction "2_2") (pintype "passive"))
    )
    (net (code "141") (name "GNDMCU") (class "Default")
      (node (ref "C1") (pin "2") (pinfunction "2_2") (pintype "passive"))
      (node (ref "C10") (pin "1") (pinfunction "1_1") (pintype "passive"))
      (node (ref "C11") (pin "2") (pinfunction "2_2") (pintype "passive"))
      (node (ref "C12") (pin "2") (pinfunction "2_2") (pintype "passive"))
      (node (ref "C13") (pin "2") (pinfunction "2_2") (pintype "passive"))
      (node (ref "C14") (pin "1") (pinfunction "1_1") (pintype "passive"))
      (node (ref "C15") (pin "1") (pinfunction "1_1") (pintype "passive"))
      (node (ref "C16") (pin "2") (pinfunction "2_2") (pintype "passive"))
      (node (ref "C17") (pin "2") (pinfunction "2_2") (pintype "passive"))
      (node (ref "C18") (pin "1") (pinfunction "1_1") (pintype "passive"))
      (node (ref "C19") (pin "2") (pinfunction "2_2") (pintype "passive"))
      (node (ref "C2") (pin "1") (pinfunction "1_1") (pintype "passive"))
      (node (ref "C20") (pin "1") (pinfunction "1_1") (pintype "passive"))
      (node (ref "C21") (pin "2") (pinfunction "2_2") (pintype "passive"))
      (node (ref "C3") (pin "2") (pinfunction "2_2") (pintype "passive"))
      (node (ref "C4") (pin "2") (pinfunction "2_2") (pintype "passive"))
      (node (ref "C5") (pin "2") (pinfunction "2_2") (pintype "passive"))
      (node (ref "C6") (pin "2") (pinfunction "2_2") (pintype "passive"))
      (node (ref "C7") (pin "1") (pinfunction "1_1") (pintype "passive"))
      (node (ref "C8") (pin "2") (pinfunction "2_2") (pintype "passive"))
      (node (ref "C9") (pin "2") (pinfunction "2_2") (pintype "passive"))
      (node (ref "EB1") (pin "2") (pinfunction "-_2") (pintype "passive"))
      (node (ref "ED1") (pin "2") (pinfunction "2_2") (pintype "passive"))
      (node (ref "ED2") (pin "2") (pintype "passive"))
      (node (ref "ED3") (pin "2") (pintype "passive"))
      (node (ref "JP3") (pin "1") (pinfunction "1_1") (pintype "passive"))
      (node (ref "M_J5") (pin "1") (pinfunction "1_1") (pintype "passive"))
      (node (ref "P3") (pin "8") (pinfunction "8_8") (pintype "passive"))
      (node (ref "P5") (pin "5") (pinfunction "5_5") (pintype "passive"))
      (node (ref "P5") (pin "6") (pinfunction "6_6") (pintype "passive"))
      (node (ref "P9") (pin "1") (pinfunction "1_1") (pintype "passive"))
      (node (ref "R2") (pin "1") (pinfunction "1_1") (pintype "passive"))
      (node (ref "R610") (pin "2") (pinfunction "2_2") (pintype "passive"))
      (node (ref "U1") (pin "1") (pinfunction "A0_1") (pintype "passive"))
      (node (ref "U1") (pin "2") (pinfunction "A1_2") (pintype "passive"))
      (node (ref "U1") (pin "3") (pinfunction "A2_3") (pintype "passive"))
      (node (ref "U1") (pin "4") (pinfunction "GND_4") (pintype "passive"))
      (node (ref "U2") (pin "4") (pinfunction "GND_4") (pintype "passive"))
      (node (ref "U3") (pin "10") (pinfunction "VSSIO_10") (pintype "passive"))
      (node (ref "U3") (pin "19") (pinfunction "VSSA_19") (pintype "passive"))
      (node (ref "U3") (pin "20") (pinfunction "VREF-_20") (pintype "passive"))
      (node (ref "U3") (pin "27") (pinfunction "VSSIO_27") (pintype "passive"))
      (node (ref "U3") (pin "49") (pinfunction "VSSIO_49") (pintype "passive"))
      (node (ref "U3") (pin "74") (pinfunction "VSSIO_74") (pintype "passive"))
      (node (ref "U3") (pin "99") (pinfunction "VSSIO_99") (pintype "passive"))
      (node (ref "U4") (pin "1") (pinfunction "GND_1") (pintype "passive"))
      (node (ref "U5") (pin "3") (pinfunction "GND_3") (pintype "passive"))
    )
    (net (code "142") (name "Net-(D1-A)") (class "Default")
      (node (ref "D1") (pin "1") (pinfunction "A_1") (pintype "passive"))
      (node (ref "EB1") (pin "1") (pinfunction "+_1") (pintype "passive"))
    )
    (net (code "143") (name "Net-(LED1-Pad1)") (class "Default")
      (node (ref "LED1") (pin "1") (pinfunction "1_1") (pintype "passive"))
      (node (ref "R5") (pin "1") (pinfunction "1_1") (pintype "passive"))
    )
    (net (code "144") (name "Net-(R608-Pad1)") (class "Default")
      (node (ref "R608") (pin "1") (pinfunction "1_1") (pintype "passive"))
      (node (ref "R609") (pin "2") (pinfunction "2_2") (pintype "passive"))
      (node (ref "U605") (pin "2") (pintype "passive"))
    )
    (net (code "145") (name "Net-(U3-PB2{slash}BOOT1)") (class "Default")
      (node (ref "R2") (pin "2") (pinfunction "2_2") (pintype "passive"))
      (node (ref "U3") (pin "37") (pinfunction "PB2/BOOT1_37") (pintype "passive"))
    )
    (net (code "146") (name "VCCDIDO") (class "Default")
      (node (ref "D4") (pin "2") (pinfunction "K_2") (pintype "passive"))
      (node (ref "JP4") (pin "2") (pinfunction "2_2") (pintype "passive"))
      (node (ref "M_J10") (pin "3") (pinfunction "3_3") (pintype "passive"))
    )
    (net (code "147") (name "VCCMCU_3.3") (class "Default")
      (node (ref "C11") (pin "1") (pinfunction "1_1") (pintype "passive"))
      (node (ref "C12") (pin "1") (pinfunction "1_1") (pintype "passive"))
      (node (ref "C13") (pin "1") (pinfunction "1_1") (pintype "passive"))
      (node (ref "C14") (pin "2") (pinfunction "2_2") (pintype "passive"))
      (node (ref "C15") (pin "2") (pinfunction "2_2") (pintype "passive"))
      (node (ref "C16") (pin "1") (pinfunction "1_1") (pintype "passive"))
      (node (ref "C2") (pin "2") (pinfunction "2_2") (pintype "passive"))
      (node (ref "C3") (pin "1") (pinfunction "1_1") (pintype "passive"))
      (node (ref "C4") (pin "1") (pinfunction "1_1") (pintype "passive"))
      (node (ref "C6") (pin "1") (pinfunction "1_1") (pintype "passive"))
      (node (ref "C8") (pin "1") (pinfunction "1_1") (pintype "passive"))
      (node (ref "D2") (pin "1") (pinfunction "A_1") (pintype "passive"))
      (node (ref "D3") (pin "2") (pinfunction "K_2") (pintype "passive"))
      (node (ref "ED2") (pin "1") (pintype "passive"))
      (node (ref "ED3") (pin "1") (pintype "passive"))
      (node (ref "P3") (pin "7") (pinfunction "7_7") (pintype "passive"))
      (node (ref "P9") (pin "2") (pinfunction "2_2") (pintype "passive"))
      (node (ref "R1") (pin "2") (pinfunction "2_2") (pintype "passive"))
      (node (ref "R3") (pin "2") (pinfunction "2_2") (pintype "passive"))
      (node (ref "R4") (pin "2") (pinfunction "2_2") (pintype "passive"))
      (node (ref "R5") (pin "2") (pinfunction "2_2") (pintype "passive"))
      (node (ref "R7") (pin "2") (pinfunction "2_2") (pintype "passive"))
      (node (ref "U1") (pin "8") (pinfunction "VCC_8") (pintype "passive"))
      (node (ref "U3") (pin "100") (pinfunction "VDDIO_100") (pintype "passive"))
      (node (ref "U3") (pin "11") (pinfunction "VDDIO_11") (pintype "passive"))
      (node (ref "U3") (pin "22") (pinfunction "VDDA_22") (pintype "passive"))
      (node (ref "U3") (pin "28") (pinfunction "VDDIO_28") (pintype "passive"))
      (node (ref "U3") (pin "50") (pinfunction "VDDIO_50") (pintype "passive"))
      (node (ref "U3") (pin "75") (pinfunction "VDDIO_75") (pintype "passive"))
      (node (ref "U4") (pin "2") (pinfunction "Vout_2") (pintype "passive"))
      (node (ref "U5") (pin "1") (pinfunction "IN_1") (pintype "passive"))
      (node (ref "U605") (pin "4") (pintype "passive"))
    )
    (net (code "148") (name "VCCMCU_5V") (class "Default")
      (node (ref "C5") (pin "1") (pinfunction "1_1") (pintype "passive"))
      (node (ref "C7") (pin "2") (pinfunction "2_2") (pintype "passive"))
      (node (ref "JP4") (pin "1") (pinfunction "1_1") (pintype "passive"))
      (node (ref "P3") (pin "5") (pinfunction "5_5") (pintype "passive"))
      (node (ref "P5") (pin "3") (pinfunction "3_3") (pintype "passive"))
      (node (ref "P5") (pin "4") (pinfunction "4_4") (pintype "passive"))
      (node (ref "U4") (pin "3") (pinfunction "Vin_3") (pintype "passive"))
    )
    (net (code "149") (name "unconnected-(DB1-CTS-Pad8)") (class "Default")
      (node (ref "DB1") (pin "8") (pinfunction "CTS_8") (pintype "passive"))
    )
    (net (code "150") (name "unconnected-(DB1-DCD-Pad1)") (class "Default")
      (node (ref "DB1") (pin "1") (pinfunction "DCD_1") (pintype "passive"))
    )
    (net (code "151") (name "unconnected-(DB1-DELL-Pad9)") (class "Default")
      (node (ref "DB1") (pin "9") (pinfunction "DELL_9") (pintype "passive"))
    )
    (net (code "152") (name "unconnected-(DB1-DSR-Pad6)") (class "Default")
      (node (ref "DB1") (pin "6") (pinfunction "DSR_6") (pintype "passive"))
    )
    (net (code "153") (name "unconnected-(DB1-DTR-Pad4)") (class "Default")
      (node (ref "DB1") (pin "4") (pinfunction "DTR_4") (pintype "passive"))
    )
    (net (code "154") (name "unconnected-(DB1-RTS-Pad7)") (class "Default")
      (node (ref "DB1") (pin "7") (pinfunction "RTS_7") (pintype "passive"))
    )
    (net (code "155") (name "unconnected-(DB2-CTS-Pad8)") (class "Default")
      (node (ref "DB2") (pin "8") (pinfunction "CTS_8") (pintype "passive"))
    )
    (net (code "156") (name "unconnected-(DB2-DCD-Pad1)") (class "Default")
      (node (ref "DB2") (pin "1") (pinfunction "DCD_1") (pintype "passive"))
    )
    (net (code "157") (name "unconnected-(DB2-DSR-Pad6)") (class "Default")
      (node (ref "DB2") (pin "6") (pinfunction "DSR_6") (pintype "passive"))
    )
    (net (code "158") (name "unconnected-(DB2-DTR-Pad4)") (class "Default")
      (node (ref "DB2") (pin "4") (pinfunction "DTR_4") (pintype "passive"))
    )
    (net (code "159") (name "unconnected-(DB2-RTS-Pad7)") (class "Default")
      (node (ref "DB2") (pin "7") (pinfunction "RTS_7") (pintype "passive"))
    )
    (net (code "160") (name "unconnected-(P2-Pad5)") (class "Default")
      (node (ref "P2") (pin "5") (pinfunction "5_5") (pintype "passive"))
    )
    (net (code "161") (name "unconnected-(U2-CLKOUT-Pad7)") (class "Default")
      (node (ref "U2") (pin "7") (pinfunction "CLKOUT_7") (pintype "passive"))
    )
    (net (code "162") (name "unconnected-(U2-~{INT}-Pad3)") (class "Default")
      (node (ref "U2") (pin "3") (pinfunction "~{INT}_3") (pintype "passive"))
    )
    (net (code "163") (name "unconnected-(U3-NC-Pad73)") (class "Default")
      (node (ref "U3") (pin "73") (pinfunction "NC_73") (pintype "tri_state"))
    )
    (net (code "164") (name "unconnected-(U3-PB1{slash}ADC12_IN9{slash}TIM3_CH4{slash}TIM8_CH3N{slash}TIM1_CH3N-Pad36)") (class "Default")
      (node (ref "U3") (pin "36") (pinfunction "PB1/ADC12_IN9/TIM3_CH4/TIM8_CH3N/TIM1_CH3N_36") (pintype "bidirectional"))
    )
    (net (code "165") (name "unconnected-(U3-PC0{slash}ADC123_IN10-Pad15)") (class "Default")
      (node (ref "U3") (pin "15") (pinfunction "PC0/ADC123_IN10_15") (pintype "bidirectional"))
    )
    (net (code "166") (name "unconnected-(U3-PC1{slash}ADC123_IN11-Pad16)") (class "Default")
      (node (ref "U3") (pin "16") (pinfunction "PC1/ADC123_IN11_16") (pintype "bidirectional"))
    )
    (net (code "167") (name "unconnected-(U3-PC13{slash}TAMPER-RTC-Pad7)") (class "Default")
      (node (ref "U3") (pin "7") (pinfunction "PC13/TAMPER-RTC_7") (pintype "bidirectional"))
    )
    (net (code "168") (name "unconnected-(U3-PE3{slash}TRACED0{slash}FSMC_A19-Pad2)") (class "Default")
      (node (ref "U3") (pin "2") (pinfunction "PE3/TRACED0/FSMC_A19_2") (pintype "bidirectional"))
    )
    (net (code "169") (name "unconnected-(U3-PE6{slash}TRACED1{slash}FSMC_A22-Pad5)") (class "Default")
      (node (ref "U3") (pin "5") (pinfunction "PE6/TRACED1/FSMC_A22_5") (pintype "bidirectional"))
    )
    (net (code "170") (name "unconnected-(U3-PE8{slash}FSMC_D5{slash}TIM1_CH1N-Pad39)") (class "Default")
      (node (ref "U3") (pin "39") (pinfunction "PE8/FSMC_D5/TIM1_CH1N_39") (pintype "bidirectional"))
    )
    (net (code "171") (name "unconnected-(U3-PE10{slash}FSMC_D7{slash}TIM1_CH2N-Pad41)") (class "Default")
      (node (ref "U3") (pin "41") (pinfunction "PE10/FSMC_D7/TIM1_CH2N_41") (pintype "bidirectional"))
    )
    (net (code "172") (name "unconnected-(U3-PE11{slash}FSMC_D8{slash}TIM1_CH2-Pad42)") (class "Default")
      (node (ref "U3") (pin "42") (pinfunction "PE11/FSMC_D8/TIM1_CH2_42") (pintype "bidirectional"))
    )
    (net (code "173") (name "unconnected-(U3-PE12{slash}FSMC_D9{slash}TIM1_CH3N-Pad43)") (class "Default")
      (node (ref "U3") (pin "43") (pinfunction "PE12/FSMC_D9/TIM1_CH3N_43") (pintype "bidirectional"))
    )
    (net (code "174") (name "unconnected-(U3-PE13{slash}FSMC_D10{slash}TIM1_CH3-Pad44)") (class "Default")
      (node (ref "U3") (pin "44") (pinfunction "PE13/FSMC_D10/TIM1_CH3_44") (pintype "bidirectional"))
    )
    (net (code "175") (name "unconnected-(U3-PE14{slash}FSMC_D11{slash}TIM1_CH4-Pad45)") (class "Default")
      (node (ref "U3") (pin "45") (pinfunction "PE14/FSMC_D11/TIM1_CH4_45") (pintype "bidirectional"))
    )
    (net (code "176") (name "unconnected-(U3-PE15{slash}FSMC_D12{slash}TIM1_BKIN-Pad46)") (class "Default")
      (node (ref "U3") (pin "46") (pinfunction "PE15/FSMC_D12/TIM1_BKIN_46") (pintype "bidirectional"))
    )
  )
)
